# PCB_control_swarm_robotics_schematic.net
KiCad netlist of a schematic drawn in Altium Designer
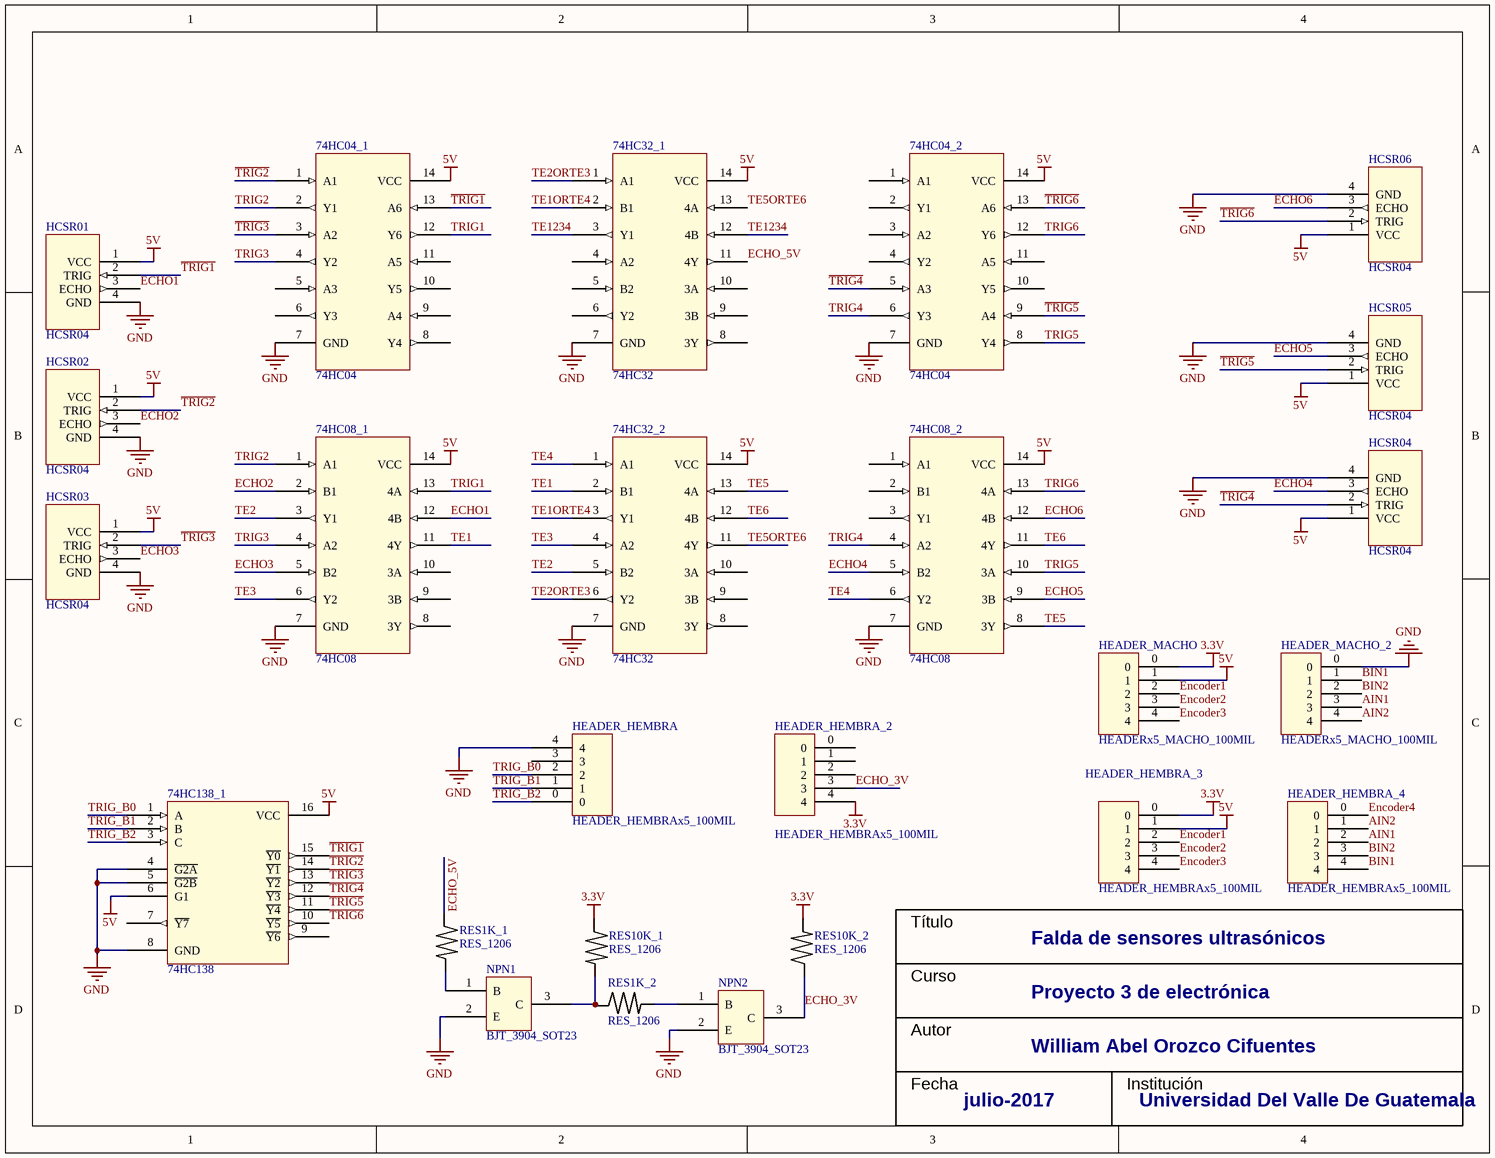
[diagram p0: PCB_control_swarm_robotics_schematic.SchDoc]

(export (version "E")
  (design (tool "Eeschema 10.0.6"))
  (components
    (comp (ref "74HC04_1")
      (value "74HC04")
      (footprint "SOIC_14_D")
      (libsource (lib "componentes_pcb_swarm_robotics") (part "74HC04"))
    )
    (comp (ref "74HC04_2")
      (value "74HC04")
      (footprint "SOIC_14_D")
      (libsource (lib "componentes_pcb_swarm_robotics") (part "74HC04"))
    )
    (comp (ref "74HC08_1")
      (value "74HC08")
      (footprint "SOIC_14_D")
      (libsource (lib "componentes_pcb_swarm_robotics") (part "74HC08"))
    )
    (comp (ref "74HC08_2")
      (value "74HC08")
      (footprint "SOIC_14_D")
      (libsource (lib "componentes_pcb_swarm_robotics") (part "74HC08"))
    )
    (comp (ref "74HC32_1")
      (value "74HC32")
      (footprint "SOIC_14_D")
      (libsource (lib "componentes_pcb_swarm_robotics") (part "74HC32"))
    )
    (comp (ref "74HC32_2")
      (value "74HC32")
      (footprint "SOIC_14_D")
      (libsource (lib "componentes_pcb_swarm_robotics") (part "74HC32"))
    )
    (comp (ref "74HC138_1")
      (value "74HC138")
      (footprint "SN74HC138DR_FOOTPRINT:SOIC16_74HC138DR")
      (libsource (lib "componentes_pcb_swarm_robotics") (part "74HC138"))
    )
    (comp (ref "HCSR01")
      (value "HCSR04")
      (footprint "HC_SR04_FOOTPRINT")
      (libsource (lib "") (part "HCSR04_1"))
    )
    (comp (ref "HCSR02")
      (value "HCSR04")
      (footprint "HC_SR04_FOOTPRINT")
      (libsource (lib "") (part "HCSR04_1"))
    )
    (comp (ref "HCSR03")
      (value "HCSR04")
      (footprint "HC_SR04_FOOTPRINT")
      (libsource (lib "") (part "HCSR04_1"))
    )
    (comp (ref "HCSR04")
      (value "HCSR04")
      (footprint "HC_SR04_FOOTPRINT")
      (libsource (lib "componentes_pcb_swarm_robotics") (part "HCSR04"))
    )
    (comp (ref "HCSR05")
      (value "HCSR04")
      (footprint "HC_SR04_FOOTPRINT")
      (libsource (lib "componentes_pcb_swarm_robotics") (part "HCSR04"))
    )
    (comp (ref "HCSR06")
      (value "HCSR04")
      (footprint "HC_SR04_FOOTPRINT")
      (libsource (lib "componentes_pcb_swarm_robotics") (part "HCSR04"))
    )
    (comp (ref "HEADER_HEMBRA")
      (value "HEADER_HEMBRAx5_100MIL")
      (footprint "HDRx5HEMBRA_FOOTPRINT")
      (libsource (lib "componentes_pcb_swarm_robotics") (part "HEADER_HEMBRAx5_100MIL"))
    )
    (comp (ref "HEADER_HEMBRA_2")
      (value "HEADER_HEMBRAx5_100MIL")
      (footprint "HDRx5HEMBRA_FOOTPRINT")
      (libsource (lib "") (part "HEADER_HEMBRAx5_100MIL_1"))
    )
    (comp (ref "HEADER_HEMBRA_3")
      (value "HEADER_HEMBRAx5_100MIL")
      (footprint "HDRx5HEMBRA_FOOTPRINT")
      (libsource (lib "") (part "HEADER_HEMBRAx5_100MIL_1"))
    )
    (comp (ref "HEADER_HEMBRA_4")
      (value "HEADER_HEMBRAx5_100MIL")
      (footprint "HDRx5HEMBRA_FOOTPRINT")
      (libsource (lib "") (part "HEADER_HEMBRAx5_100MIL_1"))
    )
    (comp (ref "HEADER_MACHO")
      (value "HEADERx5_MACHO_100MIL")
      (footprint "HEADERx5_MACHO_FOOTPRINT")
      (libsource (lib "componentes_pcb_swarm_robotics") (part "HEADERx5_MACHO_100MIL"))
    )
    (comp (ref "HEADER_MACHO_2")
      (value "HEADERx5_MACHO_100MIL")
      (footprint "HEADERx5_MACHO_FOOTPRINT")
      (libsource (lib "componentes_pcb_swarm_robotics") (part "HEADERx5_MACHO_100MIL"))
    )
    (comp (ref "NPN1")
      (value "BJT_3904_SOT23")
      (footprint "SOT23_3")
      (libsource (lib "componentes_pcb_swarm_robotics") (part "BJT_3904_SOT23"))
    )
    (comp (ref "NPN2")
      (value "BJT_3904_SOT23")
      (footprint "SOT23_3")
      (libsource (lib "componentes_pcb_swarm_robotics") (part "BJT_3904_SOT23"))
    )
    (comp (ref "RES1K_1")
      (value "RES_1206")
      (footprint "RES_SMD_1206")
      (libsource (lib "componentes_pcb_swarm_robotics") (part "RES_1206"))
    )
    (comp (ref "RES1K_2")
      (value "RES_1206")
      (footprint "RES_SMD_1206")
      (libsource (lib "componentes_pcb_swarm_robotics") (part "RES_1206"))
    )
    (comp (ref "RES10K_1")
      (value "RES_1206")
      (footprint "RES_SMD_1206")
      (libsource (lib "componentes_pcb_swarm_robotics") (part "RES_1206"))
    )
    (comp (ref "RES10K_2")
      (value "RES_1206")
      (footprint "RES_SMD_1206")
      (libsource (lib "componentes_pcb_swarm_robotics") (part "RES_1206"))
    )
  )
  (nets
    (net (code "1") (name "/AIN1") (class "Default")
      (node (ref "HEADER_HEMBRA_4") (pin "2") (pinfunction "2_2") (pintype "passive"))
      (node (ref "HEADER_MACHO_2") (pin "3") (pinfunction "3_3") (pintype "passive"))
    )
    (net (code "2") (name "/AIN2") (class "Default")
      (node (ref "HEADER_HEMBRA_4") (pin "1") (pinfunction "1_1") (pintype "passive"))
      (node (ref "HEADER_MACHO_2") (pin "4") (pinfunction "4_4") (pintype "passive"))
    )
    (net (code "3") (name "/BIN1") (class "Default")
      (node (ref "HEADER_HEMBRA_4") (pin "4") (pinfunction "4_4") (pintype "passive"))
      (node (ref "HEADER_MACHO_2") (pin "1") (pinfunction "1_1") (pintype "passive"))
    )
    (net (code "4") (name "/BIN2") (class "Default")
      (node (ref "HEADER_HEMBRA_4") (pin "3") (pinfunction "3_3") (pintype "passive"))
      (node (ref "HEADER_MACHO_2") (pin "2") (pinfunction "2_2") (pintype "passive"))
    )
    (net (code "5") (name "/ECHO1") (class "Default")
      (node (ref "74HC08_1") (pin "12") (pinfunction "4B_12") (pintype "input"))
      (node (ref "HCSR01") (pin "3") (pinfunction "ECHO_3") (pintype "output"))
    )
    (net (code "6") (name "/ECHO2") (class "Default")
      (node (ref "74HC08_1") (pin "2") (pinfunction "B1_2") (pintype "input"))
      (node (ref "HCSR02") (pin "3") (pinfunction "ECHO_3") (pintype "output"))
    )
    (net (code "7") (name "/ECHO3") (class "Default")
      (node (ref "74HC08_1") (pin "5") (pinfunction "B2_5") (pintype "input"))
      (node (ref "HCSR03") (pin "3") (pinfunction "ECHO_3") (pintype "output"))
    )
    (net (code "8") (name "/ECHO4") (class "Default")
      (node (ref "74HC08_2") (pin "5") (pinfunction "B2_5") (pintype "input"))
      (node (ref "HCSR04") (pin "3") (pinfunction "ECHO_3") (pintype "output"))
    )
    (net (code "9") (name "/ECHO5") (class "Default")
      (node (ref "74HC08_2") (pin "9") (pinfunction "3B_9") (pintype "input"))
      (node (ref "HCSR05") (pin "3") (pinfunction "ECHO_3") (pintype "output"))
    )
    (net (code "10") (name "/ECHO6") (class "Default")
      (node (ref "74HC08_2") (pin "12") (pinfunction "4B_12") (pintype "input"))
      (node (ref "HCSR06") (pin "3") (pinfunction "ECHO_3") (pintype "output"))
    )
    (net (code "11") (name "/ECHO_3V") (class "Default")
      (node (ref "HEADER_HEMBRA_2") (pin "3") (pinfunction "3_3") (pintype "passive"))
      (node (ref "NPN2") (pin "3") (pinfunction "C_3") (pintype "passive"))
      (node (ref "RES10K_2") (pin "1") (pinfunction "1_1") (pintype "passive"))
    )
    (net (code "12") (name "/ECHO_5V") (class "Default")
      (node (ref "74HC32_1") (pin "11") (pinfunction "4Y_11") (pintype "output"))
      (node (ref "RES1K_1") (pin "1") (pinfunction "1_1") (pintype "passive"))
    )
    (net (code "13") (name "/Encoder1") (class "Default")
      (node (ref "HEADER_HEMBRA_3") (pin "2") (pinfunction "2_2") (pintype "passive"))
      (node (ref "HEADER_MACHO") (pin "2") (pinfunction "2_2") (pintype "passive"))
    )
    (net (code "14") (name "/Encoder2") (class "Default")
      (node (ref "HEADER_HEMBRA_3") (pin "3") (pinfunction "3_3") (pintype "passive"))
      (node (ref "HEADER_MACHO") (pin "3") (pinfunction "3_3") (pintype "passive"))
    )
    (net (code "15") (name "/Encoder3") (class "Default")
      (node (ref "HEADER_HEMBRA_3") (pin "4") (pinfunction "4_4") (pintype "passive"))
      (node (ref "HEADER_MACHO") (pin "4") (pinfunction "4_4") (pintype "passive"))
    )
    (net (code "16") (name "/Encoder4") (class "Default")
      (node (ref "HEADER_HEMBRA_4") (pin "0") (pinfunction "0_0") (pintype "passive"))
    )
    (net (code "17") (name "/TE1") (class "Default")
      (node (ref "74HC08_1") (pin "11") (pinfunction "4Y_11") (pintype "output"))
      (node (ref "74HC32_2") (pin "2") (pinfunction "B1_2") (pintype "input"))
    )
    (net (code "18") (name "/TE1ORTE4") (class "Default")
      (node (ref "74HC32_1") (pin "2") (pinfunction "B1_2") (pintype "input"))
      (node (ref "74HC32_2") (pin "3") (pinfunction "Y1_3") (pintype "output"))
    )
    (net (code "19") (name "/TE2") (class "Default")
      (node (ref "74HC08_1") (pin "3") (pinfunction "Y1_3") (pintype "output"))
      (node (ref "74HC32_2") (pin "5") (pinfunction "B2_5") (pintype "input"))
    )
    (net (code "20") (name "/TE2ORTE3") (class "Default")
      (node (ref "74HC32_1") (pin "1") (pinfunction "A1_1") (pintype "input"))
      (node (ref "74HC32_2") (pin "6") (pinfunction "Y2_6") (pintype "output"))
    )
    (net (code "21") (name "/TE3") (class "Default")
      (node (ref "74HC08_1") (pin "6") (pinfunction "Y2_6") (pintype "output"))
      (node (ref "74HC32_2") (pin "4") (pinfunction "A2_4") (pintype "input"))
    )
    (net (code "22") (name "/TE4") (class "Default")
      (node (ref "74HC08_2") (pin "6") (pinfunction "Y2_6") (pintype "output"))
      (node (ref "74HC32_2") (pin "1") (pinfunction "A1_1") (pintype "input"))
    )
    (net (code "23") (name "/TE5") (class "Default")
      (node (ref "74HC08_2") (pin "8") (pinfunction "3Y_8") (pintype "output"))
      (node (ref "74HC32_2") (pin "13") (pinfunction "4A_13") (pintype "input"))
    )
    (net (code "24") (name "/TE5ORTE6") (class "Default")
      (node (ref "74HC32_1") (pin "13") (pinfunction "4A_13") (pintype "input"))
      (node (ref "74HC32_2") (pin "11") (pinfunction "4Y_11") (pintype "output"))
    )
    (net (code "25") (name "/TE6") (class "Default")
      (node (ref "74HC08_2") (pin "11") (pinfunction "4Y_11") (pintype "output"))
      (node (ref "74HC32_2") (pin "12") (pinfunction "4B_12") (pintype "input"))
    )
    (net (code "26") (name "/TE1234") (class "Default")
      (node (ref "74HC32_1") (pin "12") (pinfunction "4B_12") (pintype "input"))
      (node (ref "74HC32_1") (pin "3") (pinfunction "Y1_3") (pintype "output"))
    )
    (net (code "27") (name "/TRIG1") (class "Default")
      (node (ref "74HC04_1") (pin "12") (pinfunction "Y6_12") (pintype "output"))
      (node (ref "74HC08_1") (pin "13") (pinfunction "4A_13") (pintype "input"))
    )
    (net (code "28") (name "/TRIG2") (class "Default")
      (node (ref "74HC04_1") (pin "2") (pinfunction "Y1_2") (pintype "output"))
      (node (ref "74HC08_1") (pin "1") (pinfunction "A1_1") (pintype "input"))
    )
    (net (code "29") (name "/TRIG3") (class "Default")
      (node (ref "74HC04_1") (pin "4") (pinfunction "Y2_4") (pintype "output"))
      (node (ref "74HC08_1") (pin "4") (pinfunction "A2_4") (pintype "input"))
    )
    (net (code "30") (name "/TRIG4") (class "Default")
      (node (ref "74HC04_2") (pin "6") (pinfunction "Y3_6") (pintype "output"))
      (node (ref "74HC08_2") (pin "4") (pinfunction "A2_4") (pintype "input"))
    )
    (net (code "31") (name "/TRIG5") (class "Default")
      (node (ref "74HC04_2") (pin "8") (pinfunction "Y4_8") (pintype "output"))
      (node (ref "74HC08_2") (pin "10") (pinfunction "3A_10") (pintype "input"))
    )
    (net (code "32") (name "/TRIG6") (class "Default")
      (node (ref "74HC04_2") (pin "12") (pinfunction "Y6_12") (pintype "output"))
      (node (ref "74HC08_2") (pin "13") (pinfunction "4A_13") (pintype "input"))
    )
    (net (code "33") (name "/TRIG_B0") (class "Default")
      (node (ref "74HC138_1") (pin "1") (pinfunction "A_1") (pintype "input"))
      (node (ref "HEADER_HEMBRA") (pin "2") (pinfunction "2_2") (pintype "passive"))
    )
    (net (code "34") (name "/TRIG_B1") (class "Default")
      (node (ref "74HC138_1") (pin "2") (pinfunction "B_2") (pintype "input"))
      (node (ref "HEADER_HEMBRA") (pin "1") (pinfunction "1_1") (pintype "passive"))
    )
    (net (code "35") (name "/TRIG_B2") (class "Default")
      (node (ref "74HC138_1") (pin "3") (pinfunction "C_3") (pintype "input"))
      (node (ref "HEADER_HEMBRA") (pin "0") (pinfunction "0_0") (pintype "passive"))
    )
    (net (code "36") (name "/~{TRIG1}") (class "Default")
      (node (ref "74HC04_1") (pin "13") (pinfunction "A6_13") (pintype "input"))
      (node (ref "74HC138_1") (pin "15") (pinfunction "~{Y0}_15") (pintype "output"))
      (node (ref "HCSR01") (pin "2") (pinfunction "TRIG_2") (pintype "input"))
    )
    (net (code "37") (name "/~{TRIG2}") (class "Default")
      (node (ref "74HC04_1") (pin "1") (pinfunction "A1_1") (pintype "input"))
      (node (ref "74HC138_1") (pin "14") (pinfunction "~{Y1}_14") (pintype "output"))
      (node (ref "HCSR02") (pin "2") (pinfunction "TRIG_2") (pintype "input"))
    )
    (net (code "38") (name "/~{TRIG3}") (class "Default")
      (node (ref "74HC04_1") (pin "3") (pinfunction "A2_3") (pintype "input"))
      (node (ref "74HC138_1") (pin "13") (pinfunction "~{Y2}_13") (pintype "output"))
      (node (ref "HCSR03") (pin "2") (pinfunction "TRIG_2") (pintype "input"))
    )
    (net (code "39") (name "/~{TRIG4}") (class "Default")
      (node (ref "74HC04_2") (pin "5") (pinfunction "A3_5") (pintype "input"))
      (node (ref "74HC138_1") (pin "12") (pinfunction "~{Y3}_12") (pintype "output"))
      (node (ref "HCSR04") (pin "2") (pinfunction "TRIG_2") (pintype "input"))
    )
    (net (code "40") (name "/~{TRIG5}") (class "Default")
      (node (ref "74HC04_2") (pin "9") (pinfunction "A4_9") (pintype "input"))
      (node (ref "74HC138_1") (pin "11") (pinfunction "~{Y4}_11") (pintype "output"))
      (node (ref "HCSR05") (pin "2") (pinfunction "TRIG_2") (pintype "input"))
    )
    (net (code "41") (name "/~{TRIG6}") (class "Default")
      (node (ref "74HC04_2") (pin "13") (pinfunction "A6_13") (pintype "input"))
      (node (ref "74HC138_1") (pin "10") (pinfunction "~{Y5}_10") (pintype "output"))
      (node (ref "HCSR06") (pin "2") (pinfunction "TRIG_2") (pintype "input"))
    )
    (net (code "42") (name "3.3V") (class "Default")
      (node (ref "HEADER_HEMBRA_2") (pin "4") (pinfunction "4_4") (pintype "passive"))
      (node (ref "HEADER_HEMBRA_3") (pin "0") (pinfunction "0_0") (pintype "passive"))
      (node (ref "HEADER_MACHO") (pin "0") (pinfunction "0_0") (pintype "passive"))
      (node (ref "RES10K_1") (pin "1") (pinfunction "1_1") (pintype "passive"))
      (node (ref "RES10K_2") (pin "2") (pinfunction "2_2") (pintype "passive"))
    )
    (net (code "43") (name "5V") (class "Default")
      (node (ref "74HC04_1") (pin "14") (pinfunction "VCC_14") (pintype "power_in"))
      (node (ref "74HC04_2") (pin "14") (pinfunction "VCC_14") (pintype "power_in"))
      (node (ref "74HC08_1") (pin "14") (pinfunction "VCC_14") (pintype "power_in"))
      (node (ref "74HC08_2") (pin "14") (pinfunction "VCC_14") (pintype "power_in"))
      (node (ref "74HC138_1") (pin "16") (pinfunction "VCC_16") (pintype "power_in"))
      (node (ref "74HC138_1") (pin "6") (pinfunction "G1_6") (pintype "passive"))
      (node (ref "74HC32_1") (pin "14") (pinfunction "VCC_14") (pintype "power_in"))
      (node (ref "74HC32_2") (pin "14") (pinfunction "VCC_14") (pintype "power_in"))
      (node (ref "HCSR01") (pin "1") (pinfunction "VCC_1") (pintype "power_in"))
      (node (ref "HCSR02") (pin "1") (pinfunction "VCC_1") (pintype "power_in"))
      (node (ref "HCSR03") (pin "1") (pinfunction "VCC_1") (pintype "power_in"))
      (node (ref "HCSR04") (pin "1") (pinfunction "VCC_1") (pintype "power_in"))
      (node (ref "HCSR05") (pin "1") (pinfunction "VCC_1") (pintype "power_in"))
      (node (ref "HCSR06") (pin "1") (pinfunction "VCC_1") (pintype "power_in"))
      (node (ref "HEADER_HEMBRA_3") (pin "1") (pinfunction "1_1") (pintype "passive"))
      (node (ref "HEADER_MACHO") (pin "1") (pinfunction "1_1") (pintype "passive"))
    )
    (net (code "44") (name "GND") (class "Default")
      (node (ref "74HC04_1") (pin "7") (pinfunction "GND_7") (pintype "power_in"))
      (node (ref "74HC04_2") (pin "7") (pinfunction "GND_7") (pintype "power_in"))
      (node (ref "74HC08_1") (pin "7") (pinfunction "GND_7") (pintype "power_in"))
      (node (ref "74HC08_2") (pin "7") (pinfunction "GND_7") (pintype "power_in"))
      (node (ref "74HC138_1") (pin "4") (pinfunction "~{G2A}_4") (pintype "passive"))
      (node (ref "74HC138_1") (pin "5") (pinfunction "~{G2B}_5") (pintype "passive"))
      (node (ref "74HC138_1") (pin "8") (pinfunction "GND_8") (pintype "power_in"))
      (node (ref "74HC32_1") (pin "7") (pinfunction "GND_7") (pintype "power_in"))
      (node (ref "74HC32_2") (pin "7") (pinfunction "GND_7") (pintype "power_in"))
      (node (ref "HCSR01") (pin "4") (pinfunction "GND_4") (pintype "power_in"))
      (node (ref "HCSR02") (pin "4") (pinfunction "GND_4") (pintype "power_in"))
      (node (ref "HCSR03") (pin "4") (pinfunction "GND_4") (pintype "power_in"))
      (node (ref "HCSR04") (pin "4") (pinfunction "GND_4") (pintype "power_in"))
      (node (ref "HCSR05") (pin "4") (pinfunction "GND_4") (pintype "power_in"))
      (node (ref "HCSR06") (pin "4") (pinfunction "GND_4") (pintype "power_in"))
      (node (ref "HEADER_HEMBRA") (pin "4") (pinfunction "4_4") (pintype "passive"))
      (node (ref "HEADER_MACHO_2") (pin "0") (pinfunction "0_0") (pintype "passive"))
      (node (ref "NPN1") (pin "2") (pinfunction "E_2") (pintype "passive"))
      (node (ref "NPN2") (pin "2") (pinfunction "E_2") (pintype "passive"))
    )
    (net (code "45") (name "Net-(NPN1-B)") (class "Default")
      (node (ref "NPN1") (pin "1") (pinfunction "B_1") (pintype "passive"))
      (node (ref "RES1K_1") (pin "2") (pinfunction "2_2") (pintype "passive"))
    )
    (net (code "46") (name "Net-(NPN1-C)") (class "Default")
      (node (ref "NPN1") (pin "3") (pinfunction "C_3") (pintype "passive"))
      (node (ref "RES10K_1") (pin "2") (pinfunction "2_2") (pintype "passive"))
      (node (ref "RES1K_2") (pin "1") (pinfunction "1_1") (pintype "passive"))
    )
    (net (code "47") (name "Net-(NPN2-B)") (class "Default")
      (node (ref "NPN2") (pin "1") (pinfunction "B_1") (pintype "passive"))
      (node (ref "RES1K_2") (pin "2") (pinfunction "2_2") (pintype "passive"))
    )
    (net (code "48") (name "unconnected-(74HC04_1-A3-Pad5)") (class "Default")
      (node (ref "74HC04_1") (pin "5") (pinfunction "A3_5") (pintype "input"))
    )
    (net (code "49") (name "unconnected-(74HC04_1-A4-Pad9)") (class "Default")
      (node (ref "74HC04_1") (pin "9") (pinfunction "A4_9") (pintype "input"))
    )
    (net (code "50") (name "unconnected-(74HC04_1-A5-Pad11)") (class "Default")
      (node (ref "74HC04_1") (pin "11") (pinfunction "A5_11") (pintype "input"))
    )
    (net (code "51") (name "unconnected-(74HC04_1-Y3-Pad6)") (class "Default")
      (node (ref "74HC04_1") (pin "6") (pinfunction "Y3_6") (pintype "output"))
    )
    (net (code "52") (name "unconnected-(74HC04_1-Y4-Pad8)") (class "Default")
      (node (ref "74HC04_1") (pin "8") (pinfunction "Y4_8") (pintype "output"))
    )
    (net (code "53") (name "unconnected-(74HC04_1-Y5-Pad10)") (class "Default")
      (node (ref "74HC04_1") (pin "10") (pinfunction "Y5_10") (pintype "output"))
    )
    (net (code "54") (name "unconnected-(74HC04_2-A1-Pad1)") (class "Default")
      (node (ref "74HC04_2") (pin "1") (pinfunction "A1_1") (pintype "input"))
    )
    (net (code "55") (name "unconnected-(74HC04_2-A2-Pad3)") (class "Default")
      (node (ref "74HC04_2") (pin "3") (pinfunction "A2_3") (pintype "input"))
    )
    (net (code "56") (name "unconnected-(74HC04_2-A5-Pad11)") (class "Default")
      (node (ref "74HC04_2") (pin "11") (pinfunction "A5_11") (pintype "input"))
    )
    (net (code "57") (name "unconnected-(74HC04_2-Y1-Pad2)") (class "Default")
      (node (ref "74HC04_2") (pin "2") (pinfunction "Y1_2") (pintype "output"))
    )
    (net (code "58") (name "unconnected-(74HC04_2-Y2-Pad4)") (class "Default")
      (node (ref "74HC04_2") (pin "4") (pinfunction "Y2_4") (pintype "output"))
    )
    (net (code "59") (name "unconnected-(74HC04_2-Y5-Pad10)") (class "Default")
      (node (ref "74HC04_2") (pin "10") (pinfunction "Y5_10") (pintype "output"))
    )
    (net (code "60") (name "unconnected-(74HC08_1-3A-Pad10)") (class "Default")
      (node (ref "74HC08_1") (pin "10") (pinfunction "3A_10") (pintype "input"))
    )
    (net (code "61") (name "unconnected-(74HC08_1-3B-Pad9)") (class "Default")
      (node (ref "74HC08_1") (pin "9") (pinfunction "3B_9") (pintype "input"))
    )
    (net (code "62") (name "unconnected-(74HC08_1-3Y-Pad8)") (class "Default")
      (node (ref "74HC08_1") (pin "8") (pinfunction "3Y_8") (pintype "output"))
    )
    (net (code "63") (name "unconnected-(74HC08_2-A1-Pad1)") (class "Default")
      (node (ref "74HC08_2") (pin "1") (pinfunction "A1_1") (pintype "input"))
    )
    (net (code "64") (name "unconnected-(74HC08_2-B1-Pad2)") (class "Default")
      (node (ref "74HC08_2") (pin "2") (pinfunction "B1_2") (pintype "input"))
    )
    (net (code "65") (name "unconnected-(74HC08_2-Y1-Pad3)") (class "Default")
      (node (ref "74HC08_2") (pin "3") (pinfunction "Y1_3") (pintype "output"))
    )
    (net (code "66") (name "unconnected-(74HC32_1-3A-Pad10)") (class "Default")
      (node (ref "74HC32_1") (pin "10") (pinfunction "3A_10") (pintype "input"))
    )
    (net (code "67") (name "unconnected-(74HC32_1-3B-Pad9)") (class "Default")
      (node (ref "74HC32_1") (pin "9") (pinfunction "3B_9") (pintype "input"))
    )
    (net (code "68") (name "unconnected-(74HC32_1-3Y-Pad8)") (class "Default")
      (node (ref "74HC32_1") (pin "8") (pinfunction "3Y_8") (pintype "output"))
    )
    (net (code "69") (name "unconnected-(74HC32_1-A2-Pad4)") (class "Default")
      (node (ref "74HC32_1") (pin "4") (pinfunction "A2_4") (pintype "input"))
    )
    (net (code "70") (name "unconnected-(74HC32_1-B2-Pad5)") (class "Default")
      (node (ref "74HC32_1") (pin "5") (pinfunction "B2_5") (pintype "input"))
    )
    (net (code "71") (name "unconnected-(74HC32_1-Y2-Pad6)") (class "Default")
      (node (ref "74HC32_1") (pin "6") (pinfunction "Y2_6") (pintype "output"))
    )
    (net (code "72") (name "unconnected-(74HC32_2-3A-Pad10)") (class "Default")
      (node (ref "74HC32_2") (pin "10") (pinfunction "3A_10") (pintype "input"))
    )
    (net (code "73") (name "unconnected-(74HC32_2-3B-Pad9)") (class "Default")
      (node (ref "74HC32_2") (pin "9") (pinfunction "3B_9") (pintype "input"))
    )
    (net (code "74") (name "unconnected-(74HC32_2-3Y-Pad8)") (class "Default")
      (node (ref "74HC32_2") (pin "8") (pinfunction "3Y_8") (pintype "output"))
    )
    (net (code "75") (name "unconnected-(74HC138_1-~{Y6}-Pad9)") (class "Default")
      (node (ref "74HC138_1") (pin "9") (pinfunction "~{Y6}_9") (pintype "output"))
    )
    (net (code "76") (name "unconnected-(74HC138_1-~{Y7}-Pad7)") (class "Default")
      (node (ref "74HC138_1") (pin "7") (pinfunction "~{Y7}_7") (pintype "output"))
    )
    (net (code "77") (name "unconnected-(HEADER_HEMBRA-Pad3)") (class "Default")
      (node (ref "HEADER_HEMBRA") (pin "3") (pinfunction "3_3") (pintype "passive"))
    )
    (net (code "78") (name "unconnected-(HEADER_HEMBRA_2-Pad0)") (class "Default")
      (node (ref "HEADER_HEMBRA_2") (pin "0") (pinfunction "0_0") (pintype "passive"))
    )
    (net (code "79") (name "unconnected-(HEADER_HEMBRA_2-Pad1)") (class "Default")
      (node (ref "HEADER_HEMBRA_2") (pin "1") (pinfunction "1_1") (pintype "passive"))
    )
    (net (code "80") (name "unconnected-(HEADER_HEMBRA_2-Pad2)") (class "Default")
      (node (ref "HEADER_HEMBRA_2") (pin "2") (pinfunction "2_2") (pintype "passive"))
    )
  )
)
